# TopLevel.net
KiCad netlist of a schematic drawn in Altium Designer
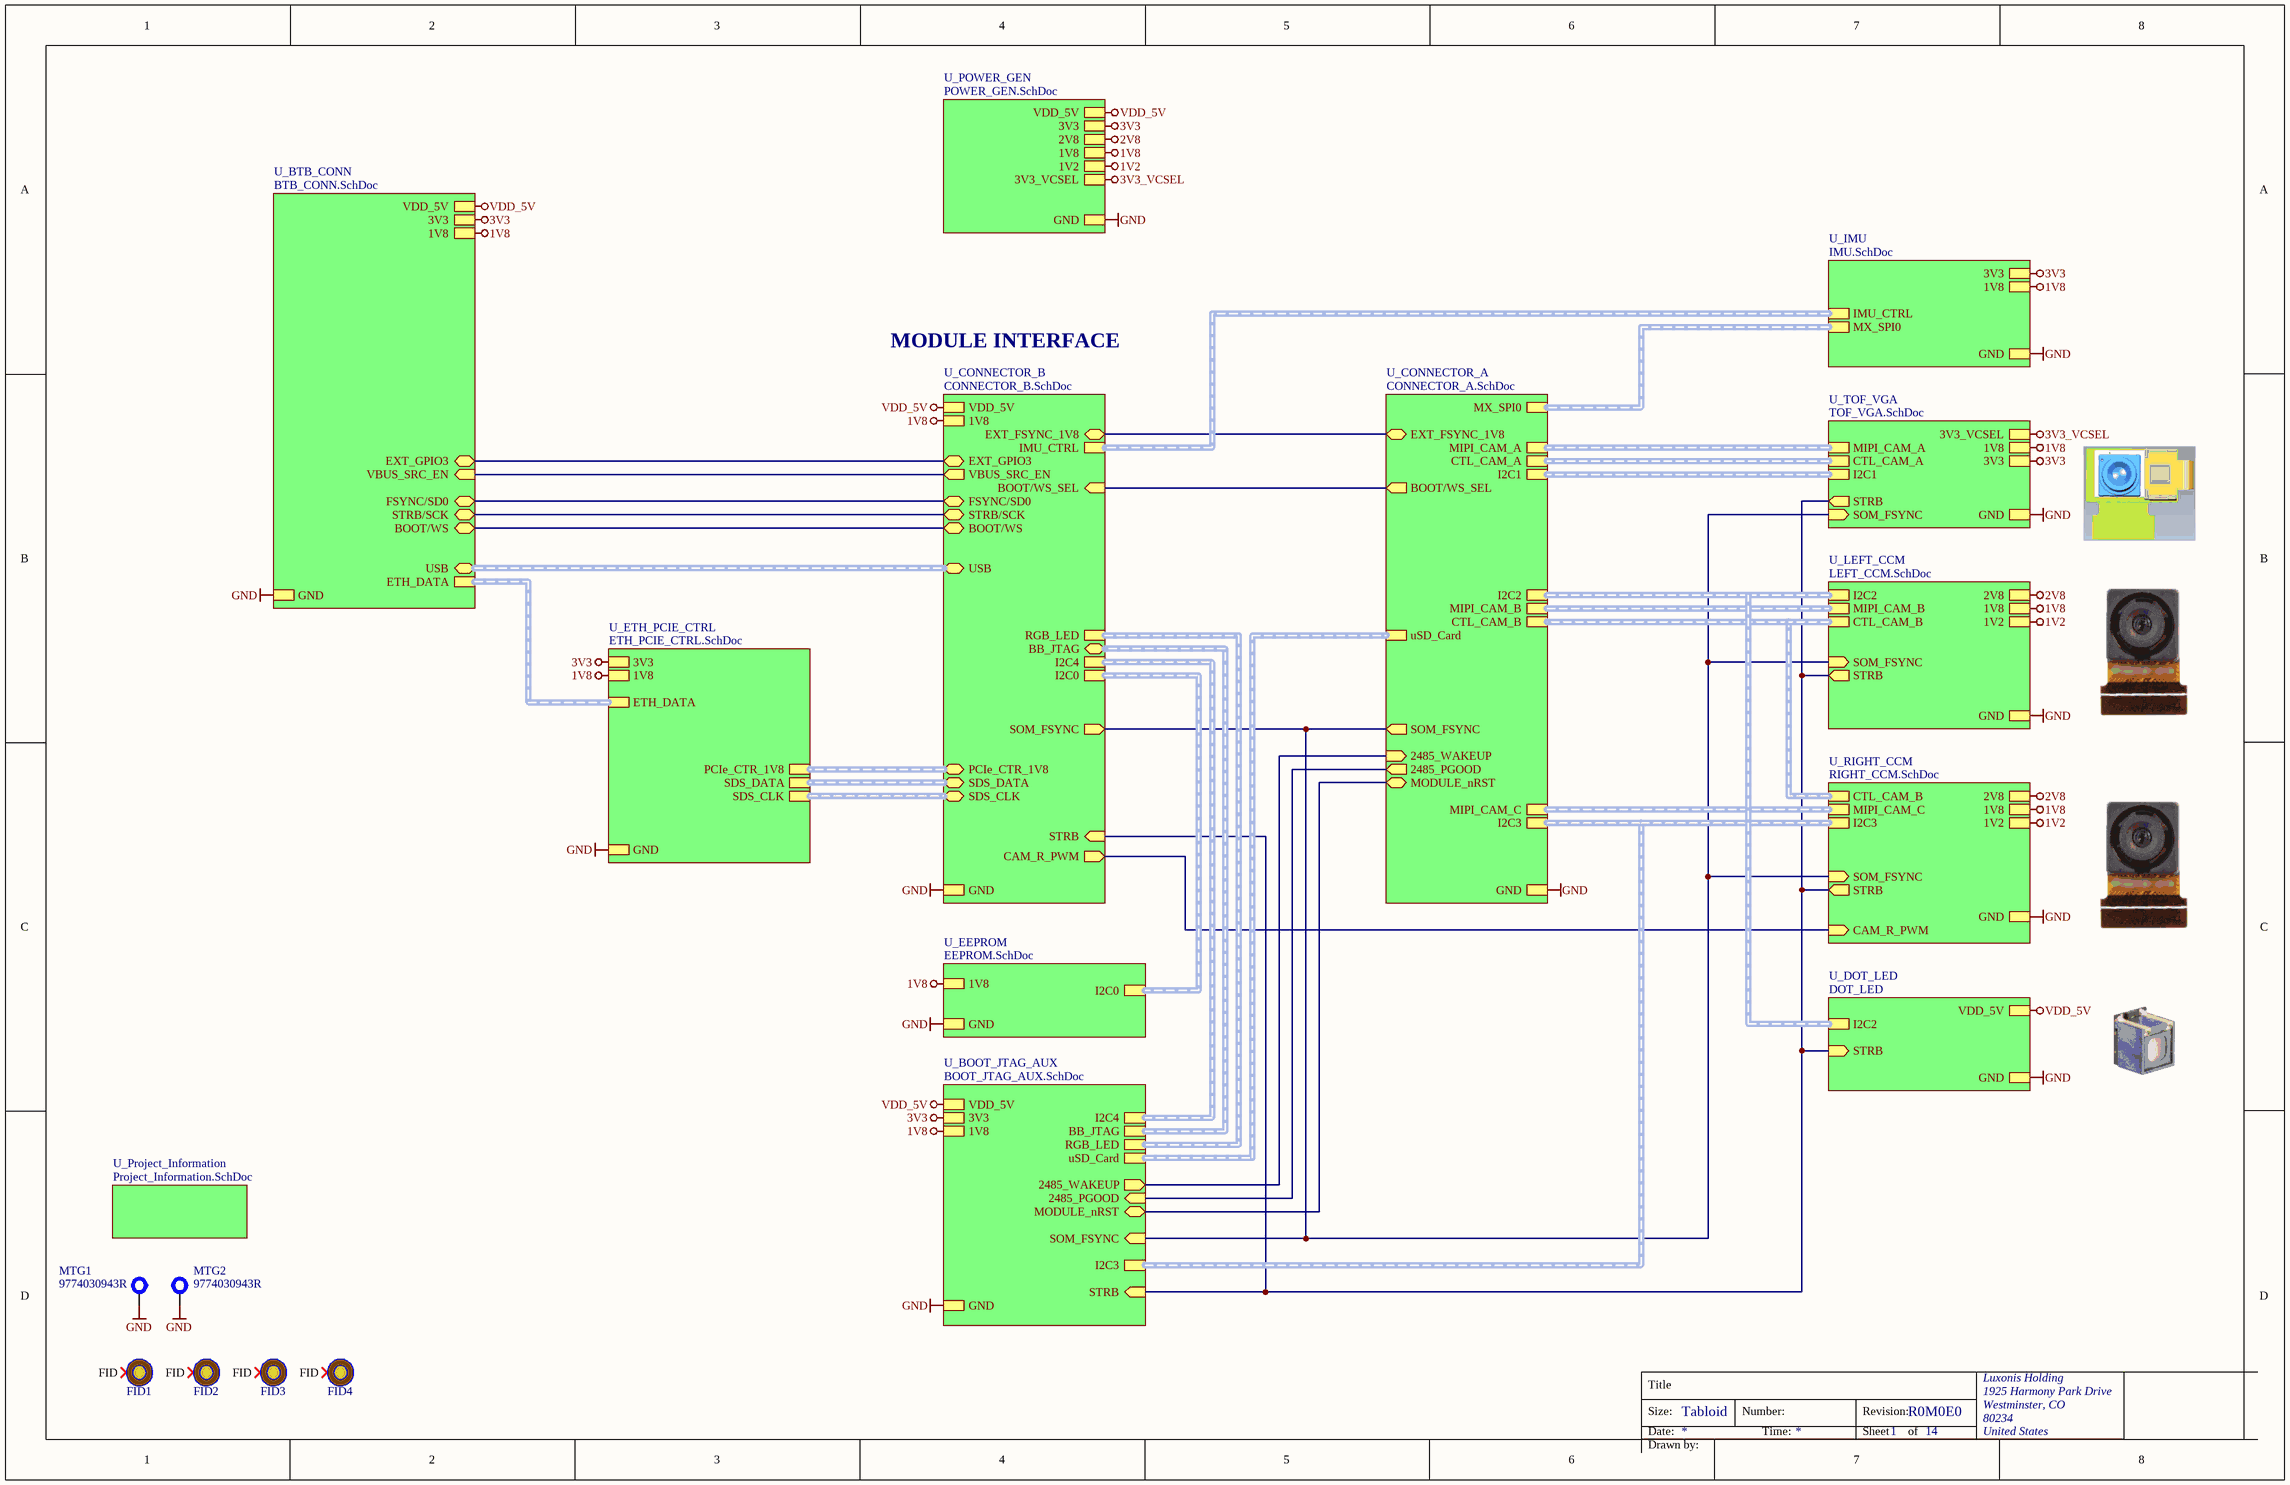
[diagram p0: TopLevel.SchDoc]

(export (version "E")
  (design (tool "Eeschema 10.0.6"))
  (components
    (comp (ref "FID1")
      (value "FIDUCIAL_ROUND_1MM")
      (footprint "LuxonisMaster:FIDUCIAL_ROUND_1MM")
      (description "Fiducial with various available footprints")
      (libsource (lib "LuxonisMaster") (part "FIDUCIAL"))
    )
    (comp (ref "FID2")
      (value "FIDUCIAL_ROUND_1MM")
      (footprint "LuxonisMaster:FIDUCIAL_ROUND_1MM")
      (description "Fiducial with various available footprints")
      (libsource (lib "LuxonisMaster") (part "FIDUCIAL"))
    )
    (comp (ref "FID3")
      (value "FIDUCIAL_ROUND_1MM")
      (footprint "LuxonisMaster:FIDUCIAL_ROUND_1MM")
      (description "Fiducial with various available footprints")
      (libsource (lib "LuxonisMaster") (part "FIDUCIAL"))
    )
    (comp (ref "FID4")
      (value "FIDUCIAL_ROUND_1MM")
      (footprint "LuxonisMaster:FIDUCIAL_ROUND_1MM")
      (description "Fiducial with various available footprints")
      (libsource (lib "LuxonisMaster") (part "FIDUCIAL"))
    )
    (comp (ref "MTG1")
      (value "9774030943R")
      (footprint "9774030943R")
      (description "Spacers/Standoffs")
      (libsource (lib "Luxonis LLC") (part "9774030943R"))
    )
    (comp (ref "MTG2")
      (value "9774030943R")
      (footprint "9774030943R")
      (description "Spacers/Standoffs")
      (libsource (lib "Luxonis LLC") (part "9774030943R"))
    )
  )
  (nets
    (net (code "39") (name "GND") (class "Default")
      (node (ref "MTG1") (pin "1") (pintype "passive"))
      (node (ref "MTG2") (pin "1") (pintype "passive"))
    )
    (net (code "41") (name "unconnected-(FID1-PadFID)") (class "Default")
      (node (ref "FID1") (pin "FID") (pinfunction "FID_FID") (pintype "input+no_connect"))
    )
    (net (code "42") (name "unconnected-(FID2-PadFID)") (class "Default")
      (node (ref "FID2") (pin "FID") (pinfunction "FID_FID") (pintype "input+no_connect"))
    )
    (net (code "43") (name "unconnected-(FID3-PadFID)") (class "Default")
      (node (ref "FID3") (pin "FID") (pinfunction "FID_FID") (pintype "input+no_connect"))
    )
    (net (code "44") (name "unconnected-(FID4-PadFID)") (class "Default")
      (node (ref "FID4") (pin "FID") (pinfunction "FID_FID") (pintype "input+no_connect"))
    )
  )
)
